# CompIoT.net
KiCad netlist of a schematic drawn in EAGLE
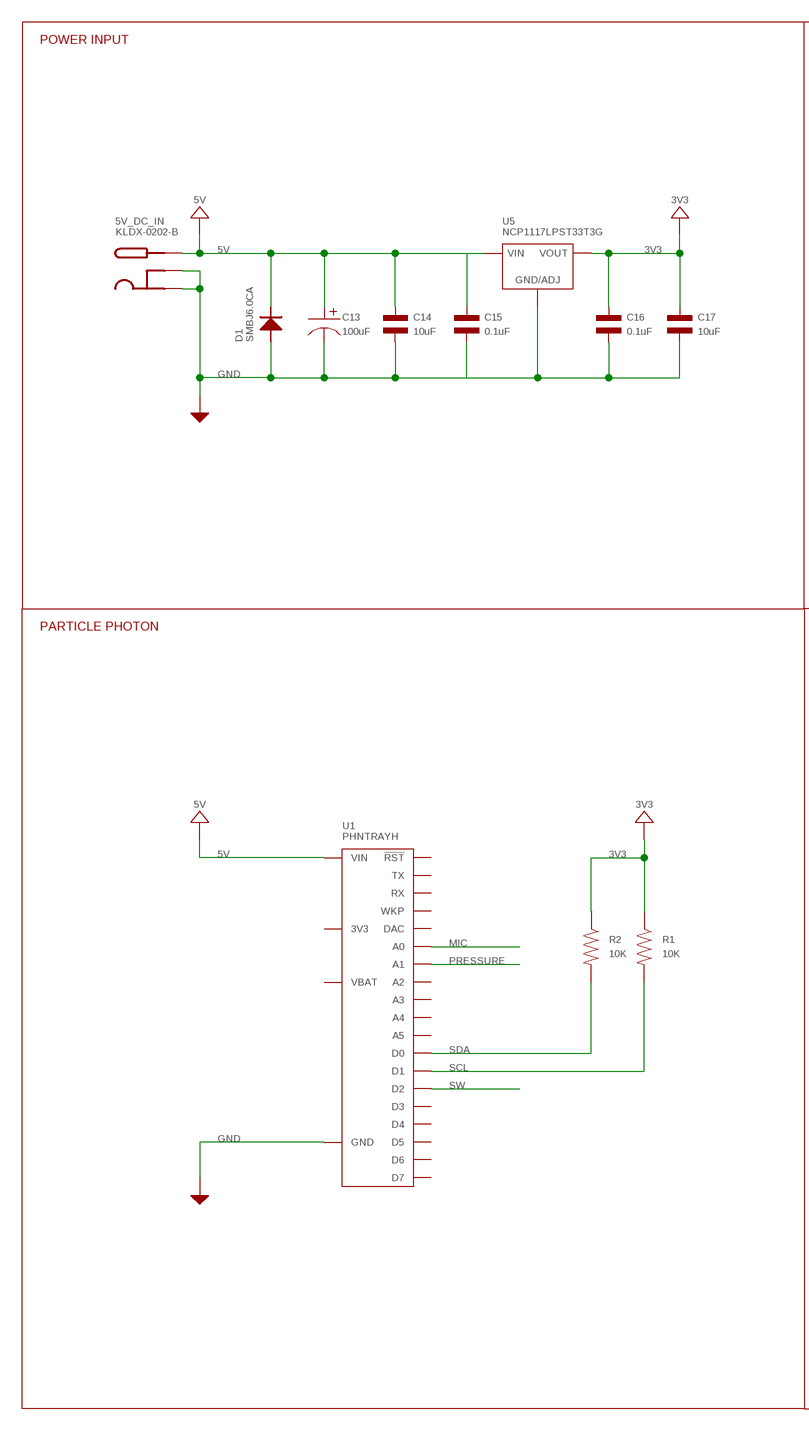
[diagram p0: schematic, sheet 1, part 1 of 2]
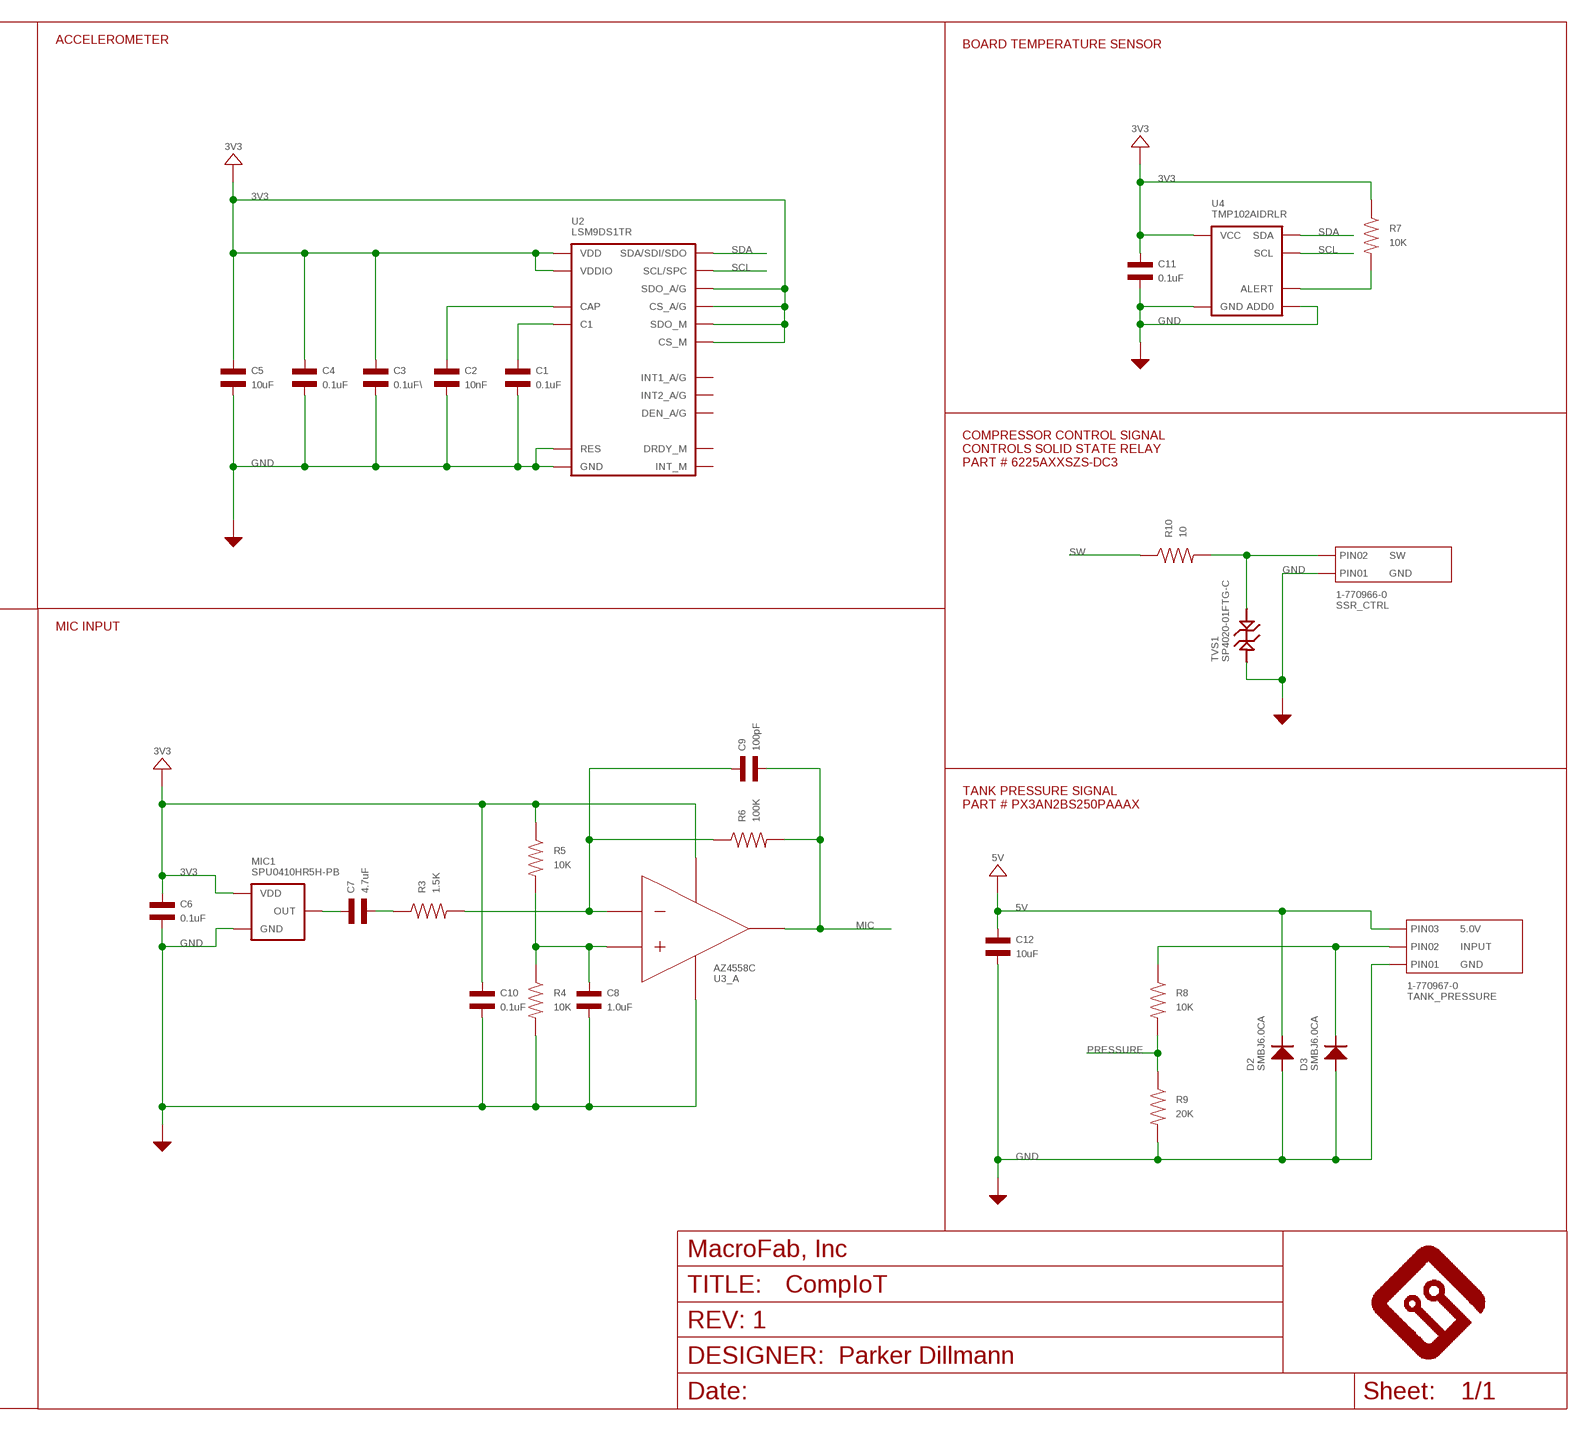
[diagram p1: schematic, sheet 1, part 2 of 2]

(export (version "E")
  (design (tool "Eeschema 10.0.6"))
  (components
    (comp (ref "5V_DC_IN")
      (value "KLDX-0202-B")
      (footprint "eagle-import:DC_PWR_JACK")
      (fields (field (name "HOUSEPART") "NO"))
      (libsource (lib "eagle-import") (part "DC_PWR_JACK_2.5MM_RIGHT"))
    )
    (comp (ref "C1")
      (value "0.1uF")
      (footprint "eagle-import:C0603")
      (libsource (lib "eagle-import") (part "CAPACITOR_NP_0603"))
    )
    (comp (ref "C2")
      (value "10nF")
      (footprint "eagle-import:C0603")
      (libsource (lib "eagle-import") (part "CAPACITOR_NP_0603"))
    )
    (comp (ref "C3")
      (value "0.1uF\\")
      (footprint "eagle-import:C0603")
      (libsource (lib "eagle-import") (part "CAPACITOR_NP_0603"))
    )
    (comp (ref "C4")
      (value "0.1uF")
      (footprint "eagle-import:C0603")
      (libsource (lib "eagle-import") (part "CAPACITOR_NP_0603"))
    )
    (comp (ref "C5")
      (value "10uF")
      (footprint "eagle-import:C1206")
      (libsource (lib "eagle-import") (part "CAPACITOR_NP_1206"))
    )
    (comp (ref "C6")
      (value "0.1uF")
      (footprint "eagle-import:C0603")
      (libsource (lib "eagle-import") (part "CAPACITOR_NP_0603"))
    )
    (comp (ref "C7")
      (value "4.7uF")
      (footprint "eagle-import:C1206")
      (libsource (lib "eagle-import") (part "CAPACITOR_NP_1206"))
    )
    (comp (ref "C8")
      (value "1.0uF")
      (footprint "eagle-import:C0603")
      (libsource (lib "eagle-import") (part "CAPACITOR_NP_0603"))
    )
    (comp (ref "C9")
      (value "100pF")
      (footprint "eagle-import:C0603")
      (libsource (lib "eagle-import") (part "CAPACITOR_NP_0603"))
    )
    (comp (ref "C10")
      (value "0.1uF")
      (footprint "eagle-import:C0603")
      (libsource (lib "eagle-import") (part "CAPACITOR_NP_0603"))
    )
    (comp (ref "C11")
      (value "0.1uF")
      (footprint "eagle-import:C0603")
      (libsource (lib "eagle-import") (part "CAPACITOR_NP_0603"))
    )
    (comp (ref "C12")
      (value "10uF")
      (footprint "eagle-import:C1206")
      (libsource (lib "eagle-import") (part "CAPACITOR_NP_1206"))
    )
    (comp (ref "C13")
      (value "100uF")
      (footprint "eagle-import:CP6.3MM")
      (libsource (lib "eagle-import") (part "CAPACITOR_P_6.3MM"))
    )
    (comp (ref "C14")
      (value "10uF")
      (footprint "eagle-import:C1206")
      (libsource (lib "eagle-import") (part "CAPACITOR_NP_1206"))
    )
    (comp (ref "C15")
      (value "0.1uF")
      (footprint "eagle-import:C0603")
      (libsource (lib "eagle-import") (part "CAPACITOR_NP_0603"))
    )
    (comp (ref "C16")
      (value "0.1uF")
      (footprint "eagle-import:C0603")
      (libsource (lib "eagle-import") (part "CAPACITOR_NP_0603"))
    )
    (comp (ref "C17")
      (value "10uF")
      (footprint "eagle-import:C1206")
      (libsource (lib "eagle-import") (part "CAPACITOR_NP_1206"))
    )
    (comp (ref "D1")
      (value "SMBJ6.0CA")
      (footprint "eagle-import:SMBJ")
      (libsource (lib "eagle-import") (part "DIODE_SMBJ"))
    )
    (comp (ref "D2")
      (value "SMBJ6.0CA")
      (footprint "eagle-import:SMBJ")
      (libsource (lib "eagle-import") (part "DIODE_SMBJ"))
    )
    (comp (ref "D3")
      (value "SMBJ6.0CA")
      (footprint "eagle-import:SMBJ")
      (libsource (lib "eagle-import") (part "DIODE_SMBJ"))
    )
    (comp (ref "FRAME1")
      (value "MF_FRAMEDEFAULT")
      (footprint "eagle-import:MF_FRAME_DEFAULT")
      (fields
        (field (name "HOUSEPART") "0")
        (field (name "DNAME") "Parker Dillmann")
        (field (name "REVNUM") "REV: 1")
      )
      (libsource (lib "eagle-import") (part "MF_FRAMEDEFAULT"))
    )
    (comp (ref "MIC1")
      (value "SPU0410HR5H-PB")
      (footprint "eagle-import:SPU0410HR5H-PB")
      (libsource (lib "eagle-import") (part "SPU0410HR5H-PB"))
    )
    (comp (ref "R1")
      (value "10K")
      (footprint "eagle-import:R0603")
      (libsource (lib "eagle-import") (part "RESISTOR_0603"))
    )
    (comp (ref "R2")
      (value "10K")
      (footprint "eagle-import:R0603")
      (libsource (lib "eagle-import") (part "RESISTOR_0603"))
    )
    (comp (ref "R3")
      (value "1.5K")
      (footprint "eagle-import:R0603")
      (libsource (lib "eagle-import") (part "RESISTOR_0603"))
    )
    (comp (ref "R4")
      (value "10K")
      (footprint "eagle-import:R0603")
      (libsource (lib "eagle-import") (part "RESISTOR_0603"))
    )
    (comp (ref "R5")
      (value "10K")
      (footprint "eagle-import:R0603")
      (libsource (lib "eagle-import") (part "RESISTOR_0603"))
    )
    (comp (ref "R6")
      (value "100K")
      (footprint "eagle-import:R0603")
      (libsource (lib "eagle-import") (part "RESISTOR_0603"))
    )
    (comp (ref "R7")
      (value "10K")
      (footprint "eagle-import:R0603")
      (libsource (lib "eagle-import") (part "RESISTOR_0603"))
    )
    (comp (ref "R8")
      (value "10K")
      (footprint "eagle-import:R0603")
      (libsource (lib "eagle-import") (part "RESISTOR_0603"))
    )
    (comp (ref "R9")
      (value "20K")
      (footprint "eagle-import:R0603")
      (libsource (lib "eagle-import") (part "RESISTOR_0603"))
    )
    (comp (ref "R10")
      (value "10")
      (footprint "eagle-import:R0603")
      (libsource (lib "eagle-import") (part "RESISTOR_0603"))
    )
    (comp (ref "SSR_CTRL")
      (value "1-770966-0")
      (footprint "eagle-import:1-770966-0")
      (fields (field (name "LABEL01") "GND") (field (name "LABEL02") "SW"))
      (libsource (lib "eagle-import") (part "CON_01X02_1-770966-0"))
    )
    (comp (ref "TANK_PRESSURE")
      (value "1-770967-0")
      (footprint "eagle-import:1-770967-0")
      (fields (field (name "LABEL01") "GND") (field (name "LABEL02") "INPUT") (field (name "LABEL03") "5.0V"))
      (libsource (lib "eagle-import") (part "CON_01X03_1-770967-0"))
    )
    (comp (ref "TVS1")
      (value "SP4020-01FTG-C")
      (footprint "eagle-import:SOD-323")
      (libsource (lib "eagle-import") (part "TVS_DIODE_SOD-323"))
    )
    (comp (ref "U1")
      (value "PHNTRAYH")
      (footprint "eagle-import:PARTICLE_PHOTON_PTH")
      (libsource (lib "eagle-import") (part "PARTICLE_PHOTON_PTH"))
    )
    (comp (ref "U2")
      (value "LSM9DS1TR")
      (footprint "eagle-import:LSM9DS1_LGA-24")
      (libsource (lib "eagle-import") (part "LSM9DS1TR"))
    )
    (comp (ref "U3")
      (value "AZ4558C")
      (footprint "eagle-import:AZ4558C_SOIC-8")
      (libsource (lib "eagle-import") (part "AZ4558C"))
    )
    (comp (ref "U4")
      (value "TMP102AIDRLR")
      (footprint "eagle-import:TMP102_SOT-553-6")
      (libsource (lib "eagle-import") (part "TMP102AIDRLR"))
    )
    (comp (ref "U5")
      (value "NCP1117LPST33T3G")
      (footprint "eagle-import:SOT-223-3")
      (fields (field (name "HOUSEPART") "NO"))
      (libsource (lib "eagle-import") (part "NCP1117LPST33T3G"))
    )
  )
  (nets
    (net (code "1") (name "/MIC") (class "Default")
      (node (ref "C9") (pin "P$2") (pinfunction "P$2_P$2") (pintype "passive"))
      (node (ref "R6") (pin "P$2") (pinfunction "P$2_P$2") (pintype "passive"))
      (node (ref "U1") (pin "12") (pinfunction "A0_12") (pintype "bidirectional"))
      (node (ref "U3") (pin "1") (pinfunction "OUTPUT_1_1") (pintype "bidirectional"))
    )
    (net (code "2") (name "/PRESSURE") (class "Default")
      (node (ref "R8") (pin "P$2") (pinfunction "P$2_P$2") (pintype "passive"))
      (node (ref "R9") (pin "P$1") (pinfunction "P$1_P$1") (pintype "passive"))
      (node (ref "U1") (pin "11") (pinfunction "A1_11") (pintype "bidirectional"))
    )
    (net (code "3") (name "/SCL") (class "Default")
      (node (ref "R1") (pin "P$2") (pinfunction "P$2_P$2") (pintype "passive"))
      (node (ref "U1") (pin "14") (pinfunction "D1_14") (pintype "bidirectional"))
      (node (ref "U2") (pin "2") (pinfunction "SCL/SPC_2") (pintype "bidirectional"))
      (node (ref "U4") (pin "1") (pinfunction "SCL_1") (pintype "bidirectional"))
    )
    (net (code "4") (name "/SDA") (class "Default")
      (node (ref "R2") (pin "P$2") (pinfunction "P$2_P$2") (pintype "passive"))
      (node (ref "U1") (pin "13") (pinfunction "D0_13") (pintype "bidirectional"))
      (node (ref "U2") (pin "4") (pinfunction "SDA/SDI/SDO_4") (pintype "bidirectional"))
      (node (ref "U4") (pin "6") (pinfunction "SDA_6") (pintype "bidirectional"))
    )
    (net (code "5") (name "/SW") (class "Default")
      (node (ref "R10") (pin "P$1") (pinfunction "P$1_P$1") (pintype "passive"))
      (node (ref "U1") (pin "15") (pinfunction "D2_15") (pintype "bidirectional"))
    )
    (net (code "6") (name "3V3") (class "Default")
      (node (ref "C10") (pin "P$1") (pinfunction "P$1_P$1") (pintype "passive"))
      (node (ref "C11") (pin "P$1") (pinfunction "P$1_P$1") (pintype "passive"))
      (node (ref "C16") (pin "P$1") (pinfunction "P$1_P$1") (pintype "passive"))
      (node (ref "C17") (pin "P$1") (pinfunction "P$1_P$1") (pintype "passive"))
      (node (ref "C3") (pin "P$1") (pinfunction "P$1_P$1") (pintype "passive"))
      (node (ref "C4") (pin "P$1") (pinfunction "P$1_P$1") (pintype "passive"))
      (node (ref "C5") (pin "P$1") (pinfunction "P$1_P$1") (pintype "passive"))
      (node (ref "C6") (pin "P$1") (pinfunction "P$1_P$1") (pintype "passive"))
      (node (ref "MIC1") (pin "P$1") (pinfunction "VDD_P$1") (pintype "bidirectional"))
      (node (ref "R1") (pin "P$1") (pinfunction "P$1_P$1") (pintype "passive"))
      (node (ref "R2") (pin "P$1") (pinfunction "P$1_P$1") (pintype "passive"))
      (node (ref "R5") (pin "P$1") (pinfunction "P$1_P$1") (pintype "passive"))
      (node (ref "R7") (pin "P$1") (pinfunction "P$1_P$1") (pintype "passive"))
      (node (ref "U2") (pin "1") (pinfunction "VDDIO_1") (pintype "bidirectional"))
      (node (ref "U2") (pin "22") (pinfunction "VDD_22") (pintype "bidirectional"))
      (node (ref "U2") (pin "23") (pinfunction "VDD_23") (pintype "bidirectional"))
      (node (ref "U2") (pin "3") (pinfunction "VDDIO_3") (pintype "bidirectional"))
      (node (ref "U2") (pin "5") (pinfunction "SDO_A/G_5") (pintype "bidirectional"))
      (node (ref "U2") (pin "6") (pinfunction "SDO_M_6") (pintype "bidirectional"))
      (node (ref "U2") (pin "7") (pinfunction "CS_A/G_7") (pintype "bidirectional"))
      (node (ref "U2") (pin "8") (pinfunction "CS_M_8") (pintype "bidirectional"))
      (node (ref "U3") (pin "4") (pinfunction "VEE_4") (pintype "bidirectional"))
      (node (ref "U4") (pin "5") (pinfunction "VCC_5") (pintype "bidirectional"))
      (node (ref "U5") (pin "P$1") (pinfunction "VOUT_P$1") (pintype "bidirectional"))
      (node (ref "U5") (pin "P$3") (pinfunction "VOUT_P$3") (pintype "bidirectional"))
    )
    (net (code "7") (name "5V") (class "Default")
      (node (ref "5V_DC_IN") (pin "PIN") (pinfunction "PIN_PIN") (pintype "power_in"))
      (node (ref "C12") (pin "P$1") (pinfunction "P$1_P$1") (pintype "passive"))
      (node (ref "C13") (pin "P$1") (pinfunction "P$1_P$1") (pintype "passive"))
      (node (ref "C14") (pin "P$1") (pinfunction "P$1_P$1") (pintype "passive"))
      (node (ref "C15") (pin "P$1") (pinfunction "P$1_P$1") (pintype "passive"))
      (node (ref "D1") (pin "CATH") (pinfunction "CATHODE_CATH") (pintype "bidirectional"))
      (node (ref "D2") (pin "CATH") (pinfunction "CATHODE_CATH") (pintype "bidirectional"))
      (node (ref "TANK_PRESSURE") (pin "P$3") (pinfunction "PIN3_P$3") (pintype "bidirectional"))
      (node (ref "U1") (pin "1") (pinfunction "VIN_1") (pintype "bidirectional"))
      (node (ref "U5") (pin "P$4") (pinfunction "VIN_P$4") (pintype "bidirectional"))
    )
    (net (code "8") (name "GND_RAIL") (class "Default")
      (node (ref "5V_DC_IN") (pin "SLEEVE1") (pinfunction "SLEEVE_SLEEVE1") (pintype "power_in"))
      (node (ref "5V_DC_IN") (pin "SLEEVE2") (pinfunction "SLEEVE_SHUNT_SLEEVE2") (pintype "power_in"))
      (node (ref "C1") (pin "P$2") (pinfunction "P$2_P$2") (pintype "passive"))
      (node (ref "C10") (pin "P$2") (pinfunction "P$2_P$2") (pintype "passive"))
      (node (ref "C11") (pin "P$2") (pinfunction "P$2_P$2") (pintype "passive"))
      (node (ref "C12") (pin "P$2") (pinfunction "P$2_P$2") (pintype "passive"))
      (node (ref "C13") (pin "P$2") (pinfunction "P$2_P$2") (pintype "passive"))
      (node (ref "C14") (pin "P$2") (pinfunction "P$2_P$2") (pintype "passive"))
      (node (ref "C15") (pin "P$2") (pinfunction "P$2_P$2") (pintype "passive"))
      (node (ref "C16") (pin "P$2") (pinfunction "P$2_P$2") (pintype "passive"))
      (node (ref "C17") (pin "P$2") (pinfunction "P$2_P$2") (pintype "passive"))
      (node (ref "C2") (pin "P$2") (pinfunction "P$2_P$2") (pintype "passive"))
      (node (ref "C3") (pin "P$2") (pinfunction "P$2_P$2") (pintype "passive"))
      (node (ref "C4") (pin "P$2") (pinfunction "P$2_P$2") (pintype "passive"))
      (node (ref "C5") (pin "P$2") (pinfunction "P$2_P$2") (pintype "passive"))
      (node (ref "C6") (pin "P$2") (pinfunction "P$2_P$2") (pintype "passive"))
      (node (ref "C8") (pin "P$2") (pinfunction "P$2_P$2") (pintype "passive"))
      (node (ref "D1") (pin "ANODE") (pinfunction "ANODE_ANODE") (pintype "bidirectional"))
      (node (ref "D2") (pin "ANODE") (pinfunction "ANODE_ANODE") (pintype "bidirectional"))
      (node (ref "D3") (pin "ANODE") (pinfunction "ANODE_ANODE") (pintype "bidirectional"))
      (node (ref "MIC1") (pin "P$2") (pinfunction "GND_P$2") (pintype "bidirectional"))
      (node (ref "MIC1") (pin "P$3") (pinfunction "GND_P$3") (pintype "bidirectional"))
      (node (ref "R4") (pin "P$2") (pinfunction "P$2_P$2") (pintype "passive"))
      (node (ref "R9") (pin "P$2") (pinfunction "P$2_P$2") (pintype "passive"))
      (node (ref "SSR_CTRL") (pin "P$1") (pinfunction "PIN1_P$1") (pintype "bidirectional"))
      (node (ref "TANK_PRESSURE") (pin "P$1") (pinfunction "PIN1_P$1") (pintype "bidirectional"))
      (node (ref "TVS1") (pin "ANODE") (pinfunction "P$1_ANODE") (pintype "bidirectional"))
      (node (ref "U1") (pin "2") (pinfunction "GND_2") (pintype "bidirectional"))
      (node (ref "U1") (pin "21") (pinfunction "GND_21") (pintype "bidirectional"))
      (node (ref "U2") (pin "14") (pinfunction "RES_14") (pintype "bidirectional"))
      (node (ref "U2") (pin "15") (pinfunction "RES_15") (pintype "bidirectional"))
      (node (ref "U2") (pin "16") (pinfunction "RES_16") (pintype "bidirectional"))
      (node (ref "U2") (pin "17") (pinfunction "RES_17") (pintype "bidirectional"))
      (node (ref "U2") (pin "18") (pinfunction "RES_18") (pintype "bidirectional"))
      (node (ref "U2") (pin "19") (pinfunction "GND_19") (pintype "bidirectional"))
      (node (ref "U2") (pin "20") (pinfunction "GND_20") (pintype "bidirectional"))
      (node (ref "U3") (pin "8") (pinfunction "VCC_8") (pintype "bidirectional"))
      (node (ref "U4") (pin "2") (pinfunction "GND_2") (pintype "bidirectional"))
      (node (ref "U4") (pin "4") (pinfunction "ADD0_4") (pintype "bidirectional"))
      (node (ref "U5") (pin "P$2") (pinfunction "GND/ADJ_P$2") (pintype "bidirectional"))
    )
    (net (code "9") (name "Net-(C7-PadP$2)") (class "Default")
      (node (ref "C7") (pin "P$2") (pinfunction "P$2_P$2") (pintype "passive"))
      (node (ref "R3") (pin "P$1") (pinfunction "P$1_P$1") (pintype "passive"))
    )
    (net (code "10") (name "Net-(D3-CATHODE)") (class "Default")
      (node (ref "D3") (pin "CATH") (pinfunction "CATHODE_CATH") (pintype "bidirectional"))
      (node (ref "R8") (pin "P$1") (pinfunction "P$1_P$1") (pintype "passive"))
      (node (ref "TANK_PRESSURE") (pin "P$2") (pinfunction "PIN2_P$2") (pintype "bidirectional"))
    )
    (net (code "11") (name "Net-(MIC1-OUT)") (class "Default")
      (node (ref "C7") (pin "P$1") (pinfunction "P$1_P$1") (pintype "passive"))
      (node (ref "MIC1") (pin "P$4") (pinfunction "OUT_P$4") (pintype "bidirectional"))
    )
    (net (code "12") (name "Net-(SSR_CTRL-PIN2)") (class "Default")
      (node (ref "R10") (pin "P$2") (pinfunction "P$2_P$2") (pintype "passive"))
      (node (ref "SSR_CTRL") (pin "P$2") (pinfunction "PIN2_P$2") (pintype "bidirectional"))
      (node (ref "TVS1") (pin "CATH") (pinfunction "P$2_CATH") (pintype "bidirectional"))
    )
    (net (code "13") (name "Net-(U2-C1)") (class "Default")
      (node (ref "C1") (pin "P$1") (pinfunction "P$1_P$1") (pintype "passive"))
      (node (ref "U2") (pin "24") (pinfunction "C1_24") (pintype "bidirectional"))
    )
    (net (code "14") (name "Net-(U2-CAP)") (class "Default")
      (node (ref "C2") (pin "P$1") (pinfunction "P$1_P$1") (pintype "passive"))
      (node (ref "U2") (pin "21") (pinfunction "CAP_21") (pintype "bidirectional"))
    )
    (net (code "15") (name "Net-(U3A-INPUT_1+)") (class "Default")
      (node (ref "C8") (pin "P$1") (pinfunction "P$1_P$1") (pintype "passive"))
      (node (ref "R4") (pin "P$1") (pinfunction "P$1_P$1") (pintype "passive"))
      (node (ref "R5") (pin "P$2") (pinfunction "P$2_P$2") (pintype "passive"))
      (node (ref "U3") (pin "3") (pinfunction "INPUT_1+_3") (pintype "bidirectional"))
    )
    (net (code "16") (name "Net-(U3A-INPUT_1-)") (class "Default")
      (node (ref "C9") (pin "P$1") (pinfunction "P$1_P$1") (pintype "passive"))
      (node (ref "R3") (pin "P$2") (pinfunction "P$2_P$2") (pintype "passive"))
      (node (ref "R6") (pin "P$1") (pinfunction "P$1_P$1") (pintype "passive"))
      (node (ref "U3") (pin "2") (pinfunction "INPUT_1-_2") (pintype "bidirectional"))
    )
    (net (code "17") (name "Net-(U4-ALERT)") (class "Default")
      (node (ref "R7") (pin "P$2") (pinfunction "P$2_P$2") (pintype "passive"))
      (node (ref "U4") (pin "3") (pinfunction "ALERT_3") (pintype "bidirectional"))
    )
    (net (code "18") (name "unconnected-(U1-3V3-Pad24)") (class "Default")
      (node (ref "U1") (pin "24") (pinfunction "3V3_24") (pintype "bidirectional"))
    )
    (net (code "19") (name "unconnected-(U1-A2-Pad10)") (class "Default")
      (node (ref "U1") (pin "10") (pinfunction "A2_10") (pintype "bidirectional"))
    )
    (net (code "20") (name "unconnected-(U1-A3-Pad9)") (class "Default")
      (node (ref "U1") (pin "9") (pinfunction "A3_9") (pintype "bidirectional"))
    )
    (net (code "21") (name "unconnected-(U1-A4-Pad8)") (class "Default")
      (node (ref "U1") (pin "8") (pinfunction "A4_8") (pintype "bidirectional"))
    )
    (net (code "22") (name "unconnected-(U1-A5-Pad7)") (class "Default")
      (node (ref "U1") (pin "7") (pinfunction "A5_7") (pintype "bidirectional"))
    )
    (net (code "23") (name "unconnected-(U1-D3-Pad16)") (class "Default")
      (node (ref "U1") (pin "16") (pinfunction "D3_16") (pintype "bidirectional"))
    )
    (net (code "24") (name "unconnected-(U1-D4-Pad17)") (class "Default")
      (node (ref "U1") (pin "17") (pinfunction "D4_17") (pintype "bidirectional"))
    )
    (net (code "25") (name "unconnected-(U1-D5-Pad18)") (class "Default")
      (node (ref "U1") (pin "18") (pinfunction "D5_18") (pintype "bidirectional"))
    )
    (net (code "26") (name "unconnected-(U1-D6-Pad19)") (class "Default")
      (node (ref "U1") (pin "19") (pinfunction "D6_19") (pintype "bidirectional"))
    )
    (net (code "27") (name "unconnected-(U1-D7-Pad20)") (class "Default")
      (node (ref "U1") (pin "20") (pinfunction "D7_20") (pintype "bidirectional"))
    )
    (net (code "28") (name "unconnected-(U1-DAC-Pad6)") (class "Default")
      (node (ref "U1") (pin "6") (pinfunction "DAC_6") (pintype "bidirectional"))
    )
    (net (code "29") (name "unconnected-(U1-RX-Pad4)") (class "Default")
      (node (ref "U1") (pin "4") (pinfunction "RX_4") (pintype "bidirectional"))
    )
    (net (code "30") (name "unconnected-(U1-TX-Pad3)") (class "Default")
      (node (ref "U1") (pin "3") (pinfunction "TX_3") (pintype "bidirectional"))
    )
    (net (code "31") (name "unconnected-(U1-VBAT-Pad22)") (class "Default")
      (node (ref "U1") (pin "22") (pinfunction "VBAT_22") (pintype "bidirectional"))
    )
    (net (code "32") (name "unconnected-(U1-WKP-Pad5)") (class "Default")
      (node (ref "U1") (pin "5") (pinfunction "WKP_5") (pintype "bidirectional"))
    )
    (net (code "33") (name "unconnected-(U1-~{RST}-Pad23)") (class "Default")
      (node (ref "U1") (pin "23") (pinfunction "~{RST}_23") (pintype "bidirectional"))
    )
    (net (code "34") (name "unconnected-(U2-DEN_A{slash}G-Pad13)") (class "Default")
      (node (ref "U2") (pin "13") (pinfunction "DEN_A/G_13") (pintype "bidirectional"))
    )
    (net (code "35") (name "unconnected-(U2-DRDY_M-Pad9)") (class "Default")
      (node (ref "U2") (pin "9") (pinfunction "DRDY_M_9") (pintype "bidirectional"))
    )
    (net (code "36") (name "unconnected-(U2-INT1_A{slash}G-Pad11)") (class "Default")
      (node (ref "U2") (pin "11") (pinfunction "INT1_A/G_11") (pintype "bidirectional"))
    )
    (net (code "37") (name "unconnected-(U2-INT2_A{slash}G-Pad12)") (class "Default")
      (node (ref "U2") (pin "12") (pinfunction "INT2_A/G_12") (pintype "bidirectional"))
    )
    (net (code "38") (name "unconnected-(U2-INT_M-Pad10)") (class "Default")
      (node (ref "U2") (pin "10") (pinfunction "INT_M_10") (pintype "bidirectional"))
    )
  )
)
